# ultrasonic_anemometer_pcb.net
KiCad netlist of a schematic drawn in EAGLE
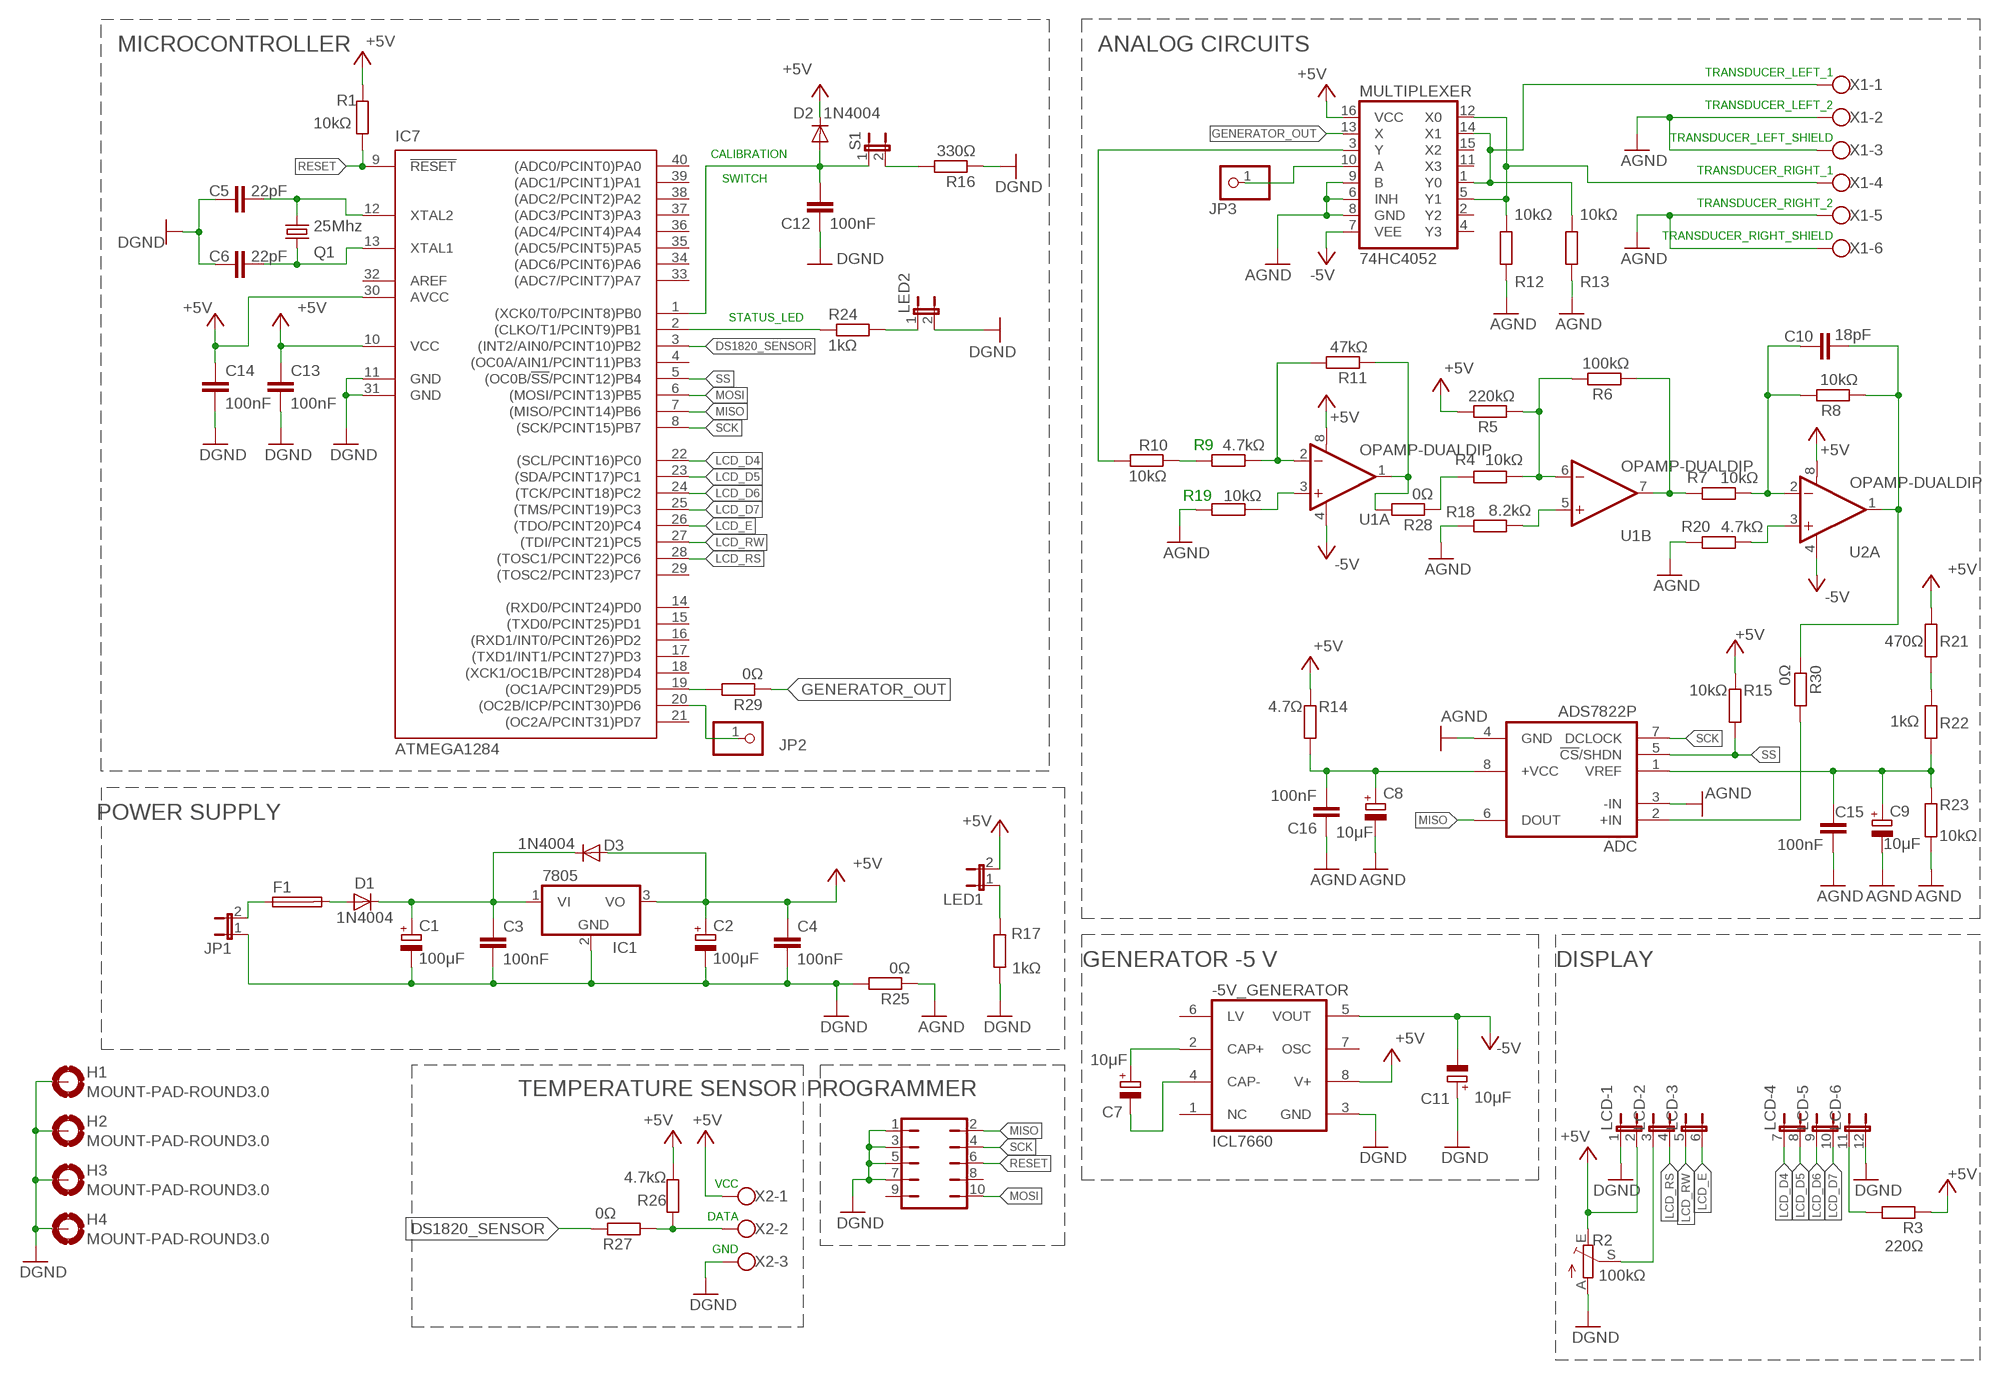
[diagram p0: schematic, sheet 1]

(export (version "E")
  (design (tool "Eeschema 10.0.6"))
  (components
    (comp (ref "-5V_GENERATOR")
      (value "ICL7660")
      (footprint "eagle-import:DIL08")
      (fields (field (name "MF") "INTERSIL") (field (name "MPN") "ICL7660CPA"))
      (libsource (lib "eagle-import") (part "ICL7660CPA"))
    )
    (comp (ref "ADC")
      (value "ADS7822P")
      (footprint "eagle-import:DIL08")
      (fields (field (name "MF") "TEXAS INSTRUMENT CONNECTORS") (field (name "MPN") "ADS7816P"))
      (libsource (lib "eagle-import") (part "ADS7816P"))
    )
    (comp (ref "C1")
      (value "100μF")
      (footprint "eagle-import:E2,5-5")
      (libsource (lib "eagle-import") (part "CPOL-EUE2.5-5"))
    )
    (comp (ref "C2")
      (value "100μF")
      (footprint "eagle-import:E2,5-5")
      (libsource (lib "eagle-import") (part "CPOL-EUE2.5-5"))
    )
    (comp (ref "C3")
      (value "100nF")
      (footprint "eagle-import:C025-025X050")
      (libsource (lib "eagle-import") (part "C-EU025-025X050"))
    )
    (comp (ref "C4")
      (value "100nF")
      (footprint "eagle-import:C025-025X050")
      (libsource (lib "eagle-import") (part "C-EU025-025X050"))
    )
    (comp (ref "C5")
      (value "22pF")
      (footprint "eagle-import:C050-024X044")
      (libsource (lib "eagle-import") (part "C-EU050-024X044"))
    )
    (comp (ref "C6")
      (value "22pF")
      (footprint "eagle-import:C050-024X044")
      (libsource (lib "eagle-import") (part "C-EU050-024X044"))
    )
    (comp (ref "C7")
      (value "10μF")
      (footprint "eagle-import:E2,5-5")
      (libsource (lib "eagle-import") (part "CPOL-EUE2.5-5"))
    )
    (comp (ref "C8")
      (value "10μF")
      (footprint "eagle-import:E2,5-5")
      (libsource (lib "eagle-import") (part "CPOL-EUE2.5-5"))
    )
    (comp (ref "C9")
      (value "10μF")
      (footprint "eagle-import:E2,5-5")
      (libsource (lib "eagle-import") (part "CPOL-EUE2.5-5"))
    )
    (comp (ref "C10")
      (value "18pF")
      (footprint "eagle-import:C050-024X044")
      (libsource (lib "eagle-import") (part "C-EU050-024X044"))
    )
    (comp (ref "C11")
      (value "10μF")
      (footprint "eagle-import:E2,5-5")
      (libsource (lib "eagle-import") (part "CPOL-EUE2.5-5"))
    )
    (comp (ref "C12")
      (value "100nF")
      (footprint "eagle-import:C025-025X050")
      (libsource (lib "eagle-import") (part "C-EU025-025X050"))
    )
    (comp (ref "C13")
      (value "100nF")
      (footprint "eagle-import:C025-025X050")
      (libsource (lib "eagle-import") (part "C-EU025-025X050"))
    )
    (comp (ref "C14")
      (value "100nF")
      (footprint "eagle-import:C025-025X050")
      (libsource (lib "eagle-import") (part "C-EU025-025X050"))
    )
    (comp (ref "C15")
      (value "100nF")
      (footprint "eagle-import:C025-025X050")
      (libsource (lib "eagle-import") (part "C-EU025-025X050"))
    )
    (comp (ref "C16")
      (value "100nF")
      (footprint "eagle-import:C025-025X050")
      (libsource (lib "eagle-import") (part "C-EU025-025X050"))
    )
    (comp (ref "D1")
      (value "1N4004")
      (footprint "eagle-import:DO41-10")
      (libsource (lib "eagle-import") (part "1N4004"))
    )
    (comp (ref "D2")
      (value "1N4004")
      (footprint "eagle-import:DO41-10")
      (libsource (lib "eagle-import") (part "1N4004"))
    )
    (comp (ref "D3")
      (value "1N4004")
      (footprint "eagle-import:DO41-10")
      (libsource (lib "eagle-import") (part "1N4004"))
    )
    (comp (ref "F1")
      (value "SH22,5A")
      (footprint "eagle-import:SH22,5A")
      (fields (field (name "MPN") "0031.7701.11"))
      (libsource (lib "eagle-import") (part "SH22,5A"))
    )
    (comp (ref "H1")
      (value "MOUNT-PAD-ROUND3.0")
      (footprint "eagle-import:3,0-PAD")
      (libsource (lib "eagle-import") (part "MOUNT-PAD-ROUND3.0"))
    )
    (comp (ref "H2")
      (value "MOUNT-PAD-ROUND3.0")
      (footprint "eagle-import:3,0-PAD")
      (libsource (lib "eagle-import") (part "MOUNT-PAD-ROUND3.0"))
    )
    (comp (ref "H3")
      (value "MOUNT-PAD-ROUND3.0")
      (footprint "eagle-import:3,0-PAD")
      (libsource (lib "eagle-import") (part "MOUNT-PAD-ROUND3.0"))
    )
    (comp (ref "H4")
      (value "MOUNT-PAD-ROUND3.0")
      (footprint "eagle-import:3,0-PAD")
      (libsource (lib "eagle-import") (part "MOUNT-PAD-ROUND3.0"))
    )
    (comp (ref "IC1")
      (value "7805")
      (footprint "eagle-import:TO220V")
      (libsource (lib "eagle-import") (part "78TV05"))
    )
    (comp (ref "IC7")
      (value "ATMEGA1284")
      (footprint "eagle-import:DIL40")
      (libsource (lib "eagle-import") (part "MEGA164P/324P/644P-PU"))
    )
    (comp (ref "JP1")
      (value "JP1E")
      (footprint "eagle-import:JP1")
      (libsource (lib "eagle-import") (part "JP1E"))
    )
    (comp (ref "JP2")
      (value "PINHD-1X1")
      (footprint "eagle-import:1X01")
      (libsource (lib "eagle-import") (part "PINHD-1X1"))
    )
    (comp (ref "JP3")
      (value "PINHD-1X1")
      (footprint "eagle-import:1X01")
      (libsource (lib "eagle-import") (part "PINHD-1X1"))
    )
    (comp (ref "LCD")
      (value "JP6QE")
      (footprint "eagle-import:JP6Q")
      (libsource (lib "eagle-import") (part "JP6QE"))
    )
    (comp (ref "LED1")
      (value "JP1E")
      (footprint "eagle-import:JP1")
      (libsource (lib "eagle-import") (part "JP1E"))
    )
    (comp (ref "LED2")
      (value "JP1E")
      (footprint "eagle-import:JP1")
      (libsource (lib "eagle-import") (part "JP1E"))
    )
    (comp (ref "MULTIPLEXER")
      (value "74HC4052")
      (footprint "eagle-import:DIL16")
      (libsource (lib "eagle-import") (part "74HC4052DIP"))
    )
    (comp (ref "PROGRAMMER")
      (value "JP5Q")
      (footprint "eagle-import:JP5Q")
      (libsource (lib "eagle-import") (part "JP5Q"))
    )
    (comp (ref "Q1")
      (value "25Mhz")
      (footprint "eagle-import:HC49_S")
      (libsource (lib "eagle-import") (part "CRYSTALHC49S"))
    )
    (comp (ref "R1")
      (value "10kΩ")
      (footprint "eagle-import:0207_10")
      (libsource (lib "eagle-import") (part "R-EU_0207/10"))
    )
    (comp (ref "R2")
      (value "100kΩ")
      (footprint "eagle-import:CA6V")
      (libsource (lib "eagle-import") (part "TRIM_EU-CA6V"))
    )
    (comp (ref "R3")
      (value "220Ω")
      (footprint "eagle-import:0207_10")
      (libsource (lib "eagle-import") (part "R-EU_0207/10"))
    )
    (comp (ref "R4")
      (value "10kΩ")
      (footprint "eagle-import:0207_10")
      (libsource (lib "eagle-import") (part "R-EU_0207/10"))
    )
    (comp (ref "R5")
      (value "220kΩ")
      (footprint "eagle-import:0207_10")
      (libsource (lib "eagle-import") (part "R-EU_0207/10"))
    )
    (comp (ref "R6")
      (value "100kΩ")
      (footprint "eagle-import:0207_10")
      (libsource (lib "eagle-import") (part "R-EU_0207/10"))
    )
    (comp (ref "R7")
      (value "10kΩ")
      (footprint "eagle-import:0207_10")
      (libsource (lib "eagle-import") (part "R-EU_0207/10"))
    )
    (comp (ref "R8")
      (value "10kΩ")
      (footprint "eagle-import:0207_10")
      (libsource (lib "eagle-import") (part "R-EU_0207/10"))
    )
    (comp (ref "R9")
      (value "4.7kΩ")
      (footprint "eagle-import:0207_10")
      (libsource (lib "eagle-import") (part "R-EU_0207/10"))
    )
    (comp (ref "R10")
      (value "10kΩ")
      (footprint "eagle-import:0207_10")
      (libsource (lib "eagle-import") (part "R-EU_0207/10"))
    )
    (comp (ref "R11")
      (value "47kΩ")
      (footprint "eagle-import:0207_10")
      (libsource (lib "eagle-import") (part "R-EU_0207/10"))
    )
    (comp (ref "R12")
      (value "10kΩ")
      (footprint "eagle-import:0207_10")
      (libsource (lib "eagle-import") (part "R-EU_0207/10"))
    )
    (comp (ref "R13")
      (value "10kΩ")
      (footprint "eagle-import:0207_10")
      (libsource (lib "eagle-import") (part "R-EU_0207/10"))
    )
    (comp (ref "R14")
      (value "4.7Ω")
      (footprint "eagle-import:0207_10")
      (libsource (lib "eagle-import") (part "R-EU_0207/10"))
    )
    (comp (ref "R15")
      (value "10kΩ")
      (footprint "eagle-import:0207_10")
      (libsource (lib "eagle-import") (part "R-EU_0207/10"))
    )
    (comp (ref "R16")
      (value "330Ω")
      (footprint "eagle-import:0207_10")
      (libsource (lib "eagle-import") (part "R-EU_0207/10"))
    )
    (comp (ref "R17")
      (value "1kΩ")
      (footprint "eagle-import:0207_10")
      (libsource (lib "eagle-import") (part "R-EU_0207/10"))
    )
    (comp (ref "R18")
      (value "8.2kΩ")
      (footprint "eagle-import:0207_10")
      (libsource (lib "eagle-import") (part "R-EU_0207/10"))
    )
    (comp (ref "R19")
      (value "10kΩ")
      (footprint "eagle-import:0207_10")
      (libsource (lib "eagle-import") (part "R-EU_0207/10"))
    )
    (comp (ref "R20")
      (value "4.7kΩ")
      (footprint "eagle-import:0207_10")
      (libsource (lib "eagle-import") (part "R-EU_0207/10"))
    )
    (comp (ref "R21")
      (value "470Ω")
      (footprint "eagle-import:0207_10")
      (libsource (lib "eagle-import") (part "R-EU_0207/10"))
    )
    (comp (ref "R22")
      (value "1kΩ")
      (footprint "eagle-import:0207_10")
      (libsource (lib "eagle-import") (part "R-EU_0207/10"))
    )
    (comp (ref "R23")
      (value "10kΩ")
      (footprint "eagle-import:0207_10")
      (libsource (lib "eagle-import") (part "R-EU_0207/10"))
    )
    (comp (ref "R24")
      (value "1kΩ")
      (footprint "eagle-import:0207_10")
      (libsource (lib "eagle-import") (part "R-EU_0207/10"))
    )
    (comp (ref "R25")
      (value "0Ω")
      (footprint "eagle-import:0207_10")
      (libsource (lib "eagle-import") (part "R-EU_0207/10"))
    )
    (comp (ref "R26")
      (value "4.7kΩ")
      (footprint "eagle-import:0207_10")
      (libsource (lib "eagle-import") (part "R-EU_0207/10"))
    )
    (comp (ref "R27")
      (value "0Ω")
      (footprint "eagle-import:0207_10")
      (libsource (lib "eagle-import") (part "R-EU_0207/10"))
    )
    (comp (ref "R28")
      (value "0Ω")
      (footprint "eagle-import:0207_10")
      (libsource (lib "eagle-import") (part "R-EU_0207/10"))
    )
    (comp (ref "R29")
      (value "0Ω")
      (footprint "eagle-import:0207_10")
      (libsource (lib "eagle-import") (part "R-EU_0207/10"))
    )
    (comp (ref "R30")
      (value "0Ω")
      (footprint "eagle-import:0207_10")
      (libsource (lib "eagle-import") (part "R-EU_0207/10"))
    )
    (comp (ref "S1")
      (value "JP1E")
      (footprint "eagle-import:JP1")
      (libsource (lib "eagle-import") (part "JP1E"))
    )
    (comp (ref "U1")
      (value "OPAMP-DUALDIP")
      (footprint "eagle-import:DIP08")
      (libsource (lib "eagle-import") (part "OPAMP-DUALDIP"))
    )
    (comp (ref "U2")
      (value "OPAMP-DUALDIP")
      (footprint "eagle-import:DIP08")
      (libsource (lib "eagle-import") (part "OPAMP-DUALDIP"))
    )
    (comp (ref "X1")
      (value "W237-6")
      (footprint "eagle-import:W237-6")
      (libsource (lib "eagle-import") (part "W237-6"))
    )
    (comp (ref "X2")
      (value "W237-103")
      (footprint "eagle-import:W237-103")
      (fields (field (name "MPN") "237-103"))
      (libsource (lib "eagle-import") (part "W237-103"))
    )
  )
  (nets
    (net (code "1") (name "+5V") (class "Default")
      (node (ref "-5V_GENERATOR") (pin "8") (pinfunction "V+_8") (pintype "power_in"))
      (node (ref "C13") (pin "1") (pinfunction "1_1") (pintype "passive"))
      (node (ref "C14") (pin "1") (pinfunction "1_1") (pintype "passive"))
      (node (ref "C2") (pin "+") (pinfunction "+_+") (pintype "passive"))
      (node (ref "C4") (pin "1") (pinfunction "1_1") (pintype "passive"))
      (node (ref "D2") (pin "C") (pinfunction "C_C") (pintype "passive"))
      (node (ref "D3") (pin "A") (pinfunction "A_A") (pintype "passive"))
      (node (ref "IC1") (pin "3") (pinfunction "VO_3") (pintype "passive"))
      (node (ref "IC7") (pin "10") (pinfunction "VCC_10") (pintype "power_in"))
      (node (ref "IC7") (pin "30") (pinfunction "AVCC_30") (pintype "power_in"))
      (node (ref "LCD") (pin "2") (pinfunction "2_2") (pintype "passive"))
      (node (ref "LED1") (pin "2") (pinfunction "2_2") (pintype "passive"))
      (node (ref "MULTIPLEXER") (pin "16") (pinfunction "VCC_16") (pintype "power_in"))
      (node (ref "R1") (pin "1") (pinfunction "1_1") (pintype "passive"))
      (node (ref "R14") (pin "1") (pinfunction "1_1") (pintype "passive"))
      (node (ref "R15") (pin "1") (pinfunction "1_1") (pintype "passive"))
      (node (ref "R2") (pin "E") (pinfunction "E_E") (pintype "passive"))
      (node (ref "R21") (pin "1") (pinfunction "1_1") (pintype "passive"))
      (node (ref "R26") (pin "1") (pinfunction "1_1") (pintype "passive"))
      (node (ref "R3") (pin "1") (pinfunction "1_1") (pintype "passive"))
      (node (ref "R5") (pin "2") (pinfunction "2_2") (pintype "passive"))
      (node (ref "U1") (pin "8") (pinfunction "V+_8") (pintype "power_in"))
      (node (ref "U2") (pin "8") (pinfunction "V+_8") (pintype "power_in"))
      (node (ref "X2") (pin "1") (pinfunction "KL_1") (pintype "passive"))
    )
    (net (code "2") (name "-5V") (class "Default")
      (node (ref "-5V_GENERATOR") (pin "5") (pinfunction "VOUT_5") (pintype "output"))
      (node (ref "C11") (pin "-") (pinfunction "-_-") (pintype "passive"))
      (node (ref "MULTIPLEXER") (pin "7") (pinfunction "VEE_7") (pintype "power_in"))
      (node (ref "U1") (pin "4") (pinfunction "V-_4") (pintype "power_in"))
      (node (ref "U2") (pin "4") (pinfunction "V-_4") (pintype "power_in"))
    )
    (net (code "3") (name "/AREF") (class "Default")
      (node (ref "IC7") (pin "32") (pinfunction "AREF_32") (pintype "power_in"))
    )
    (net (code "4") (name "AGND") (class "Default")
      (node (ref "ADC") (pin "3") (pinfunction "-IN_3") (pintype "input"))
      (node (ref "ADC") (pin "4") (pinfunction "GND_4") (pintype "power_in"))
      (node (ref "C15") (pin "1") (pinfunction "1_1") (pintype "passive"))
      (node (ref "C16") (pin "2") (pinfunction "2_2") (pintype "passive"))
      (node (ref "C8") (pin "-") (pinfunction "-_-") (pintype "passive"))
      (node (ref "C9") (pin "-") (pinfunction "-_-") (pintype "passive"))
      (node (ref "MULTIPLEXER") (pin "6") (pinfunction "INH_6") (pintype "input"))
      (node (ref "MULTIPLEXER") (pin "8") (pinfunction "GND_8") (pintype "power_in"))
      (node (ref "MULTIPLEXER") (pin "9") (pinfunction "B_9") (pintype "input"))
      (node (ref "R12") (pin "2") (pinfunction "2_2") (pintype "passive"))
      (node (ref "R13") (pin "2") (pinfunction "2_2") (pintype "passive"))
      (node (ref "R18") (pin "2") (pinfunction "2_2") (pintype "passive"))
      (node (ref "R19") (pin "2") (pinfunction "2_2") (pintype "passive"))
      (node (ref "R20") (pin "2") (pinfunction "2_2") (pintype "passive"))
      (node (ref "R23") (pin "2") (pinfunction "2_2") (pintype "passive"))
      (node (ref "R25") (pin "1") (pinfunction "1_1") (pintype "passive"))
      (node (ref "X1") (pin "2") (pinfunction "KL_2") (pintype "passive"))
      (node (ref "X1") (pin "3") (pinfunction "KL_3") (pintype "passive"))
      (node (ref "X1") (pin "5") (pinfunction "KL_5") (pintype "passive"))
      (node (ref "X1") (pin "6") (pinfunction "KL_6") (pintype "passive"))
    )
    (net (code "5") (name "DGND") (class "Default")
      (node (ref "-5V_GENERATOR") (pin "3") (pinfunction "GND_3") (pintype "power_in"))
      (node (ref "C1") (pin "-") (pinfunction "-_-") (pintype "passive"))
      (node (ref "C11") (pin "+") (pinfunction "+_+") (pintype "passive"))
      (node (ref "C12") (pin "2") (pinfunction "2_2") (pintype "passive"))
      (node (ref "C13") (pin "2") (pinfunction "2_2") (pintype "passive"))
      (node (ref "C14") (pin "2") (pinfunction "2_2") (pintype "passive"))
      (node (ref "C2") (pin "-") (pinfunction "-_-") (pintype "passive"))
      (node (ref "C3") (pin "2") (pinfunction "2_2") (pintype "passive"))
      (node (ref "C4") (pin "2") (pinfunction "2_2") (pintype "passive"))
      (node (ref "C5") (pin "1") (pinfunction "1_1") (pintype "passive"))
      (node (ref "C6") (pin "1") (pinfunction "1_1") (pintype "passive"))
      (node (ref "H1") (pin "B3,0") (pinfunction "MOUNT_B3,0") (pintype "passive"))
      (node (ref "H2") (pin "B3,0") (pinfunction "MOUNT_B3,0") (pintype "passive"))
      (node (ref "H3") (pin "B3,0") (pinfunction "MOUNT_B3,0") (pintype "passive"))
      (node (ref "H4") (pin "B3,0") (pinfunction "MOUNT_B3,0") (pintype "passive"))
      (node (ref "IC1") (pin "2") (pinfunction "GND_2") (pintype "passive"))
      (node (ref "IC7") (pin "11") (pinfunction "GND_11") (pintype "power_in"))
      (node (ref "IC7") (pin "31") (pinfunction "GND_31") (pintype "power_in"))
      (node (ref "JP1") (pin "1") (pinfunction "1_1") (pintype "passive"))
      (node (ref "LCD") (pin "1") (pinfunction "1_1") (pintype "passive"))
      (node (ref "LCD") (pin "12") (pinfunction "2_12") (pintype "passive"))
      (node (ref "LED2") (pin "2") (pinfunction "2_2") (pintype "passive"))
      (node (ref "PROGRAMMER") (pin "1") (pinfunction "1_1") (pintype "passive"))
      (node (ref "PROGRAMMER") (pin "3") (pinfunction "3_3") (pintype "passive"))
      (node (ref "PROGRAMMER") (pin "5") (pinfunction "5_5") (pintype "passive"))
      (node (ref "PROGRAMMER") (pin "7") (pinfunction "7_7") (pintype "passive"))
      (node (ref "R16") (pin "1") (pinfunction "1_1") (pintype "passive"))
      (node (ref "R17") (pin "2") (pinfunction "2_2") (pintype "passive"))
      (node (ref "R2") (pin "A") (pinfunction "A_A") (pintype "passive"))
      (node (ref "R25") (pin "2") (pinfunction "2_2") (pintype "passive"))
      (node (ref "X2") (pin "3") (pinfunction "KL_3") (pintype "passive"))
    )
    (net (code "6") (name "DS1820_SENSOR") (class "Default")
      (node (ref "IC7") (pin "3") (pinfunction "(INT2/AIN0/PCINT10)PB2_3") (pintype "bidirectional"))
      (node (ref "R27") (pin "2") (pinfunction "2_2") (pintype "passive"))
    )
    (net (code "7") (name "GENERATOR_OUT") (class "Default")
      (node (ref "MULTIPLEXER") (pin "13") (pinfunction "X_13") (pintype "bidirectional"))
      (node (ref "R29") (pin "1") (pinfunction "1_1") (pintype "passive"))
    )
    (net (code "8") (name "LCD_D4") (class "Default")
      (node (ref "IC7") (pin "22") (pinfunction "(SCL/PCINT16)PC0_22") (pintype "bidirectional"))
      (node (ref "LCD") (pin "7") (pinfunction "1_7") (pintype "passive"))
    )
    (net (code "9") (name "LCD_D5") (class "Default")
      (node (ref "IC7") (pin "23") (pinfunction "(SDA/PCINT17)PC1_23") (pintype "bidirectional"))
      (node (ref "LCD") (pin "8") (pinfunction "2_8") (pintype "passive"))
    )
    (net (code "10") (name "LCD_D6") (class "Default")
      (node (ref "IC7") (pin "24") (pinfunction "(TCK/PCINT18)PC2_24") (pintype "bidirectional"))
      (node (ref "LCD") (pin "9") (pinfunction "1_9") (pintype "passive"))
    )
    (net (code "11") (name "LCD_D7") (class "Default")
      (node (ref "IC7") (pin "25") (pinfunction "(TMS/PCINT19)PC3_25") (pintype "bidirectional"))
      (node (ref "LCD") (pin "10") (pinfunction "2_10") (pintype "passive"))
    )
    (net (code "12") (name "LCD_E") (class "Default")
      (node (ref "IC7") (pin "26") (pinfunction "(TDO/PCINT20)PC4_26") (pintype "bidirectional"))
      (node (ref "LCD") (pin "6") (pinfunction "2_6") (pintype "passive"))
    )
    (net (code "13") (name "LCD_RS") (class "Default")
      (node (ref "IC7") (pin "28") (pinfunction "(TOSC1/PCINT22)PC6_28") (pintype "bidirectional"))
      (node (ref "LCD") (pin "4") (pinfunction "2_4") (pintype "passive"))
    )
    (net (code "14") (name "LCD_RW") (class "Default")
      (node (ref "IC7") (pin "27") (pinfunction "(TDI/PCINT21)PC5_27") (pintype "bidirectional"))
      (node (ref "LCD") (pin "5") (pinfunction "1_5") (pintype "passive"))
    )
    (net (code "15") (name "MISO") (class "Default")
      (node (ref "ADC") (pin "6") (pinfunction "DOUT_6") (pintype "output"))
      (node (ref "IC7") (pin "7") (pinfunction "(MISO/PCINT14)PB6_7") (pintype "bidirectional"))
      (node (ref "PROGRAMMER") (pin "2") (pinfunction "2_2") (pintype "passive"))
    )
    (net (code "16") (name "MOSI") (class "Default")
      (node (ref "IC7") (pin "6") (pinfunction "(MOSI/PCINT13)PB5_6") (pintype "bidirectional"))
      (node (ref "PROGRAMMER") (pin "10") (pinfunction "10_10") (pintype "passive"))
    )
    (net (code "17") (name "Net-(-5V_GENERATOR-CAP+)") (class "Default")
      (node (ref "-5V_GENERATOR") (pin "2") (pinfunction "CAP+_2") (pintype "passive"))
      (node (ref "C7") (pin "+") (pinfunction "+_+") (pintype "passive"))
    )
    (net (code "18") (name "Net-(-5V_GENERATOR-CAP-)") (class "Default")
      (node (ref "-5V_GENERATOR") (pin "4") (pinfunction "CAP-_4") (pintype "passive"))
      (node (ref "C7") (pin "-") (pinfunction "-_-") (pintype "passive"))
    )
    (net (code "19") (name "Net-(ADC-+IN)") (class "Default")
      (node (ref "ADC") (pin "2") (pinfunction "+IN_2") (pintype "input"))
      (node (ref "R30") (pin "2") (pinfunction "2_2") (pintype "passive"))
    )
    (net (code "20") (name "Net-(ADC-+VCC)") (class "Default")
      (node (ref "ADC") (pin "8") (pinfunction "+VCC_8") (pintype "power_in"))
      (node (ref "C16") (pin "1") (pinfunction "1_1") (pintype "passive"))
      (node (ref "C8") (pin "+") (pinfunction "+_+") (pintype "passive"))
      (node (ref "R14") (pin "2") (pinfunction "2_2") (pintype "passive"))
    )
    (net (code "21") (name "Net-(ADC-VREF)") (class "Default")
      (node (ref "ADC") (pin "1") (pinfunction "VREF_1") (pintype "input"))
      (node (ref "C15") (pin "2") (pinfunction "2_2") (pintype "passive"))
      (node (ref "C9") (pin "+") (pinfunction "+_+") (pintype "passive"))
      (node (ref "R22") (pin "2") (pinfunction "2_2") (pintype "passive"))
      (node (ref "R23") (pin "1") (pinfunction "1_1") (pintype "passive"))
    )
    (net (code "22") (name "Net-(D1-PadA)") (class "Default")
      (node (ref "D1") (pin "A") (pinfunction "A_A") (pintype "passive"))
      (node (ref "F1") (pin "2") (pinfunction "2_2") (pintype "passive"))
    )
    (net (code "23") (name "Net-(F1-Pad1)") (class "Default")
      (node (ref "F1") (pin "1") (pinfunction "1_1") (pintype "passive"))
      (node (ref "JP1") (pin "2") (pinfunction "2_2") (pintype "passive"))
    )
    (net (code "24") (name "Net-(IC1-VI)") (class "Default")
      (node (ref "C1") (pin "+") (pinfunction "+_+") (pintype "passive"))
      (node (ref "C3") (pin "1") (pinfunction "1_1") (pintype "passive"))
      (node (ref "D1") (pin "C") (pinfunction "C_C") (pintype "passive"))
      (node (ref "D3") (pin "C") (pinfunction "C_C") (pintype "passive"))
      (node (ref "IC1") (pin "1") (pinfunction "VI_1") (pintype "input"))
    )
    (net (code "25") (name "Net-(IC7-(CLKO{slash}T1{slash}PCINT9)PB1)") (class "Default")
      (node (ref "IC7") (pin "2") (pinfunction "(CLKO/T1/PCINT9)PB1_2") (pintype "bidirectional"))
      (node (ref "R24") (pin "1") (pinfunction "1_1") (pintype "passive"))
    )
    (net (code "26") (name "Net-(IC7-(OC1A{slash}PCINT29)PD5)") (class "Default")
      (node (ref "IC7") (pin "19") (pinfunction "(OC1A/PCINT29)PD5_19") (pintype "bidirectional"))
      (node (ref "R29") (pin "2") (pinfunction "2_2") (pintype "passive"))
    )
    (net (code "27") (name "Net-(IC7-(OC2B{slash}ICP{slash}PCINT30)PD6)") (class "Default")
      (node (ref "IC7") (pin "20") (pinfunction "(OC2B/ICP/PCINT30)PD6_20") (pintype "bidirectional"))
      (node (ref "JP2") (pin "1") (pinfunction "1_1") (pintype "passive"))
    )
    (net (code "28") (name "Net-(IC7-(XCK0{slash}T0{slash}PCINT8)PB0)") (class "Default")
      (node (ref "C12") (pin "1") (pinfunction "1_1") (pintype "passive"))
      (node (ref "D2") (pin "A") (pinfunction "A_A") (pintype "passive"))
      (node (ref "IC7") (pin "1") (pinfunction "(XCK0/T0/PCINT8)PB0_1") (pintype "bidirectional"))
      (node (ref "S1") (pin "1") (pinfunction "1_1") (pintype "passive"))
    )
    (net (code "29") (name "Net-(IC7-XTAL1)") (class "Default")
      (node (ref "C6") (pin "2") (pinfunction "2_2") (pintype "passive"))
      (node (ref "IC7") (pin "13") (pinfunction "XTAL1_13") (pintype "input"))
      (node (ref "Q1") (pin "1") (pinfunction "1_1") (pintype "passive"))
    )
    (net (code "30") (name "Net-(IC7-XTAL2)") (class "Default")
      (node (ref "C5") (pin "2") (pinfunction "2_2") (pintype "passive"))
      (node (ref "IC7") (pin "12") (pinfunction "XTAL2_12") (pintype "output"))
      (node (ref "Q1") (pin "2") (pinfunction "2_2") (pintype "passive"))
    )
    (net (code "31") (name "Net-(LCDB-1)") (class "Default")
      (node (ref "LCD") (pin "3") (pinfunction "1_3") (pintype "passive"))
      (node (ref "R2") (pin "S") (pinfunction "S_S") (pintype "passive"))
    )
    (net (code "32") (name "Net-(LCDF-1)") (class "Default")
      (node (ref "LCD") (pin "11") (pinfunction "1_11") (pintype "passive"))
      (node (ref "R3") (pin "2") (pinfunction "2_2") (pintype "passive"))
    )
    (net (code "33") (name "Net-(LED1-Pad1)") (class "Default")
      (node (ref "LED1") (pin "1") (pinfunction "1_1") (pintype "passive"))
      (node (ref "R17") (pin "1") (pinfunction "1_1") (pintype "passive"))
    )
    (net (code "34") (name "Net-(LED2-Pad1)") (class "Default")
      (node (ref "LED2") (pin "1") (pinfunction "1_1") (pintype "passive"))
      (node (ref "R24") (pin "2") (pinfunction "2_2") (pintype "passive"))
    )
    (net (code "35") (name "Net-(MULTIPLEXER-A)") (class "Default")
      (node (ref "JP3") (pin "1") (pinfunction "1_1") (pintype "passive"))
      (node (ref "MULTIPLEXER") (pin "10") (pinfunction "A_10") (pintype "input"))
    )
    (net (code "36") (name "Net-(MULTIPLEXER-X0)") (class "Default")
      (node (ref "MULTIPLEXER") (pin "12") (pinfunction "X0_12") (pintype "bidirectional"))
      (node (ref "MULTIPLEXER") (pin "5") (pinfunction "Y1_5") (pintype "bidirectional"))
      (node (ref "R12") (pin "1") (pinfunction "1_1") (pintype "passive"))
      (node (ref "X1") (pin "4") (pinfunction "KL_4") (pintype "passive"))
    )
    (net (code "37") (name "Net-(MULTIPLEXER-X1)") (class "Default")
      (node (ref "MULTIPLEXER") (pin "1") (pinfunction "Y0_1") (pintype "bidirectional"))
      (node (ref "MULTIPLEXER") (pin "14") (pinfunction "X1_14") (pintype "bidirectional"))
      (node (ref "R13") (pin "1") (pinfunction "1_1") (pintype "passive"))
      (node (ref "X1") (pin "1") (pinfunction "KL_1") (pintype "passive"))
    )
    (net (code "38") (name "Net-(MULTIPLEXER-Y)") (class "Default")
      (node (ref "MULTIPLEXER") (pin "3") (pinfunction "Y_3") (pintype "bidirectional"))
      (node (ref "R10") (pin "1") (pinfunction "1_1") (pintype "passive"))
    )
    (net (code "39") (name "Net-(R10-Pad2)") (class "Default")
      (node (ref "R10") (pin "2") (pinfunction "2_2") (pintype "passive"))
      (node (ref "R9") (pin "2") (pinfunction "2_2") (pintype "passive"))
    )
    (net (code "40") (name "Net-(R16-Pad2)") (class "Default")
      (node (ref "R16") (pin "2") (pinfunction "2_2") (pintype "passive"))
      (node (ref "S1") (pin "2") (pinfunction "2_2") (pintype "passive"))
    )
    (net (code "41") (name "Net-(R21-Pad2)") (class "Default")
      (node (ref "R21") (pin "2") (pinfunction "2_2") (pintype "passive"))
      (node (ref "R22") (pin "1") (pinfunction "1_1") (pintype "passive"))
    )
    (net (code "42") (name "Net-(R28-Pad1)") (class "Default")
      (node (ref "R28") (pin "1") (pinfunction "1_1") (pintype "passive"))
      (node (ref "R4") (pin "2") (pinfunction "2_2") (pintype "passive"))
    )
    (net (code "43") (name "Net-(U1A-+IN)") (class "Default")
      (node (ref "R19") (pin "1") (pinfunction "1_1") (pintype "passive"))
      (node (ref "U1") (pin "3") (pinfunction "+IN_3") (pintype "input"))
    )
    (net (code "44") (name "Net-(U1A--IN)") (class "Default")
      (node (ref "R11") (pin "2") (pinfunction "2_2") (pintype "passive"))
      (node (ref "R9") (pin "1") (pinfunction "1_1") (pintype "passive"))
      (node (ref "U1") (pin "2") (pinfunction "-IN_2") (pintype "input"))
    )
    (net (code "45") (name "Net-(U1A-OUT)") (class "Default")
      (node (ref "R11") (pin "1") (pinfunction "1_1") (pintype "passive"))
      (node (ref "R28") (pin "2") (pinfunction "2_2") (pintype "passive"))
      (node (ref "U1") (pin "1") (pinfunction "OUT_1") (pintype "output"))
    )
    (net (code "46") (name "Net-(U1B-+IN)") (class "Default")
      (node (ref "R18") (pin "1") (pinfunction "1_1") (pintype "passive"))
      (node (ref "U1") (pin "5") (pinfunction "+IN_5") (pintype "input"))
    )
    (net (code "47") (name "Net-(U1B--IN)") (class "Default")
      (node (ref "R4") (pin "1") (pinfunction "1_1") (pintype "passive"))
      (node (ref "R5") (pin "1") (pinfunction "1_1") (pintype "passive"))
      (node (ref "R6") (pin "2") (pinfunction "2_2") (pintype "passive"))
      (node (ref "U1") (pin "6") (pinfunction "-IN_6") (pintype "input"))
    )
    (net (code "48") (name "Net-(U1B-OUT)") (class "Default")
      (node (ref "R6") (pin "1") (pinfunction "1_1") (pintype "passive"))
      (node (ref "R7") (pin "2") (pinfunction "2_2") (pintype "passive"))
      (node (ref "U1") (pin "7") (pinfunction "OUT_7") (pintype "output"))
    )
    (net (code "49") (name "Net-(U2A-+IN)") (class "Default")
      (node (ref "R20") (pin "1") (pinfunction "1_1") (pintype "passive"))
      (node (ref "U2") (pin "3") (pinfunction "+IN_3") (pintype "input"))
    )
    (net (code "50") (name "Net-(U2A--IN)") (class "Default")
      (node (ref "C10") (pin "2") (pinfunction "2_2") (pintype "passive"))
      (node (ref "R7") (pin "1") (pinfunction "1_1") (pintype "passive"))
      (node (ref "R8") (pin "2") (pinfunction "2_2") (pintype "passive"))
      (node (ref "U2") (pin "2") (pinfunction "-IN_2") (pintype "input"))
    )
    (net (code "51") (name "Net-(U2A-OUT)") (class "Default")
      (node (ref "C10") (pin "1") (pinfunction "1_1") (pintype "passive"))
      (node (ref "R30") (pin "1") (pinfunction "1_1") (pintype "passive"))
      (node (ref "R8") (pin "1") (pinfunction "1_1") (pintype "passive"))
      (node (ref "U2") (pin "1") (pinfunction "OUT_1") (pintype "output"))
    )
    (net (code "52") (name "Net-(X2B-KL)") (class "Default")
      (node (ref "R26") (pin "2") (pinfunction "2_2") (pintype "passive"))
      (node (ref "R27") (pin "1") (pinfunction "1_1") (pintype "passive"))
      (node (ref "X2") (pin "2") (pinfunction "KL_2") (pintype "passive"))
    )
    (net (code "53") (name "RESET") (class "Default")
      (node (ref "IC7") (pin "9") (pinfunction "~{RESET}_9") (pintype "input"))
      (node (ref "PROGRAMMER") (pin "6") (pinfunction "6_6") (pintype "passive"))
      (node (ref "R1") (pin "2") (pinfunction "2_2") (pintype "passive"))
    )
    (net (code "54") (name "SCK") (class "Default")
      (node (ref "ADC") (pin "7") (pinfunction "DCLOCK_7") (pintype "input"))
      (node (ref "IC7") (pin "8") (pinfunction "(SCK/PCINT15)PB7_8") (pintype "bidirectional"))
      (node (ref "PROGRAMMER") (pin "4") (pinfunction "4_4") (pintype "passive"))
    )
    (net (code "55") (name "SS") (class "Default")
      (node (ref "ADC") (pin "5") (pinfunction "~{CS}/SHDN_5") (pintype "input"))
      (node (ref "IC7") (pin "5") (pinfunction "(OC0B/~{SS}/PCINT12)PB4_5") (pintype "bidirectional"))
      (node (ref "R15") (pin "2") (pinfunction "2_2") (pintype "passive"))
    )
    (net (code "56") (name "unconnected-(-5V_GENERATOR-LV-Pad6)") (class "Default")
      (node (ref "-5V_GENERATOR") (pin "6") (pinfunction "LV_6") (pintype "passive"))
    )
    (net (code "57") (name "unconnected-(-5V_GENERATOR-NC-Pad1)") (class "Default")
      (node (ref "-5V_GENERATOR") (pin "1") (pinfunction "NC_1") (pintype "no_connect"))
    )
    (net (code "58") (name "unconnected-(-5V_GENERATOR-OSC-Pad7)") (class "Default")
      (node (ref "-5V_GENERATOR") (pin "7") (pinfunction "OSC_7") (pintype "output"))
    )
    (net (code "59") (name "unconnected-(IC7-(ADC0{slash}PCINT0)PA0-Pad40)") (class "Default")
      (node (ref "IC7") (pin "40") (pinfunction "(ADC0/PCINT0)PA0_40") (pintype "bidirectional"))
    )
    (net (code "60") (name "unconnected-(IC7-(ADC1{slash}PCINT1)PA1-Pad39)") (class "Default")
      (node (ref "IC7") (pin "39") (pinfunction "(ADC1/PCINT1)PA1_39") (pintype "bidirectional"))
    )
    (net (code "61") (name "unconnected-(IC7-(ADC2{slash}PCINT2)PA2-Pad38)") (class "Default")
      (node (ref "IC7") (pin "38") (pinfunction "(ADC2/PCINT2)PA2_38") (pintype "bidirectional"))
    )
    (net (code "62") (name "unconnected-(IC7-(ADC3{slash}PCINT3)PA3-Pad37)") (class "Default")
      (node (ref "IC7") (pin "37") (pinfunction "(ADC3/PCINT3)PA3_37") (pintype "bidirectional"))
    )
    (net (code "63") (name "unconnected-(IC7-(ADC4{slash}PCINT4)PA4-Pad36)") (class "Default")
      (node (ref "IC7") (pin "36") (pinfunction "(ADC4/PCINT4)PA4_36") (pintype "bidirectional"))
    )
    (net (code "64") (name "unconnected-(IC7-(ADC5{slash}PCINT5)PA5-Pad35)") (class "Default")
      (node (ref "IC7") (pin "35") (pinfunction "(ADC5/PCINT5)PA5_35") (pintype "bidirectional"))
    )
    (net (code "65") (name "unconnected-(IC7-(ADC6{slash}PCINT6)PA6-Pad34)") (class "Default")
      (node (ref "IC7") (pin "34") (pinfunction "(ADC6/PCINT6)PA6_34") (pintype "bidirectional"))
    )
    (net (code "66") (name "unconnected-(IC7-(ADC7{slash}PCINT7)PA7-Pad33)") (class "Default")
      (node (ref "IC7") (pin "33") (pinfunction "(ADC7/PCINT7)PA7_33") (pintype "bidirectional"))
    )
    (net (code "67") (name "unconnected-(IC7-(OC0A{slash}AIN1{slash}PCINT11)PB3-Pad4)") (class "Default")
      (node (ref "IC7") (pin "4") (pinfunction "(OC0A/AIN1/PCINT11)PB3_4") (pintype "bidirectional"))
    )
    (net (code "68") (name "unconnected-(IC7-(OC2A{slash}PCINT31)PD7-Pad21)") (class "Default")
      (node (ref "IC7") (pin "21") (pinfunction "(OC2A/PCINT31)PD7_21") (pintype "bidirectional"))
    )
    (net (code "69") (name "unconnected-(IC7-(RXD0{slash}PCINT24)PD0-Pad14)") (class "Default")
      (node (ref "IC7") (pin "14") (pinfunction "(RXD0/PCINT24)PD0_14") (pintype "bidirectional"))
    )
    (net (code "70") (name "unconnected-(IC7-(RXD1{slash}INT0{slash}PCINT26)PD2-Pad16)") (class "Default")
      (node (ref "IC7") (pin "16") (pinfunction "(RXD1/INT0/PCINT26)PD2_16") (pintype "bidirectional"))
    )
    (net (code "71") (name "unconnected-(IC7-(TOSC2{slash}PCINT23)PC7-Pad29)") (class "Default")
      (node (ref "IC7") (pin "29") (pinfunction "(TOSC2/PCINT23)PC7_29") (pintype "bidirectional"))
    )
    (net (code "72") (name "unconnected-(IC7-(TXD0{slash}PCINT25)PD1-Pad15)") (class "Default")
      (node (ref "IC7") (pin "15") (pinfunction "(TXD0/PCINT25)PD1_15") (pintype "bidirectional"))
    )
    (net (code "73") (name "unconnected-(IC7-(TXD1{slash}INT1{slash}PCINT27)PD3-Pad17)") (class "Default")
      (node (ref "IC7") (pin "17") (pinfunction "(TXD1/INT1/PCINT27)PD3_17") (pintype "bidirectional"))
    )
    (net (code "74") (name "unconnected-(IC7-(XCK1{slash}OC1B{slash}PCINT28)PD4-Pad18)") (class "Default")
      (node (ref "IC7") (pin "18") (pinfunction "(XCK1/OC1B/PCINT28)PD4_18") (pintype "bidirectional"))
    )
    (net (code "75") (name "unconnected-(MULTIPLEXER-X2-Pad15)") (class "Default")
      (node (ref "MULTIPLEXER") (pin "15") (pinfunction "X2_15") (pintype "bidirectional"))
    )
    (net (code "76") (name "unconnected-(MULTIPLEXER-X3-Pad11)") (class "Default")
      (node (ref "MULTIPLEXER") (pin "11") (pinfunction "X3_11") (pintype "bidirectional"))
    )
    (net (code "77") (name "unconnected-(MULTIPLEXER-Y2-Pad2)") (class "Default")
      (node (ref "MULTIPLEXER") (pin "2") (pinfunction "Y2_2") (pintype "bidirectional"))
    )
    (net (code "78") (name "unconnected-(MULTIPLEXER-Y3-Pad4)") (class "Default")
      (node (ref "MULTIPLEXER") (pin "4") (pinfunction "Y3_4") (pintype "bidirectional"))
    )
    (net (code "79") (name "unconnected-(PROGRAMMER-Pad8)") (class "Default")
      (node (ref "PROGRAMMER") (pin "8") (pinfunction "8_8") (pintype "passive"))
    )
    (net (code "80") (name "unconnected-(PROGRAMMER-Pad9)") (class "Default")
      (node (ref "PROGRAMMER") (pin "9") (pinfunction "9_9") (pintype "passive"))
    )
  )
)
